# v2.net
KiCad netlist of a schematic drawn in EAGLE
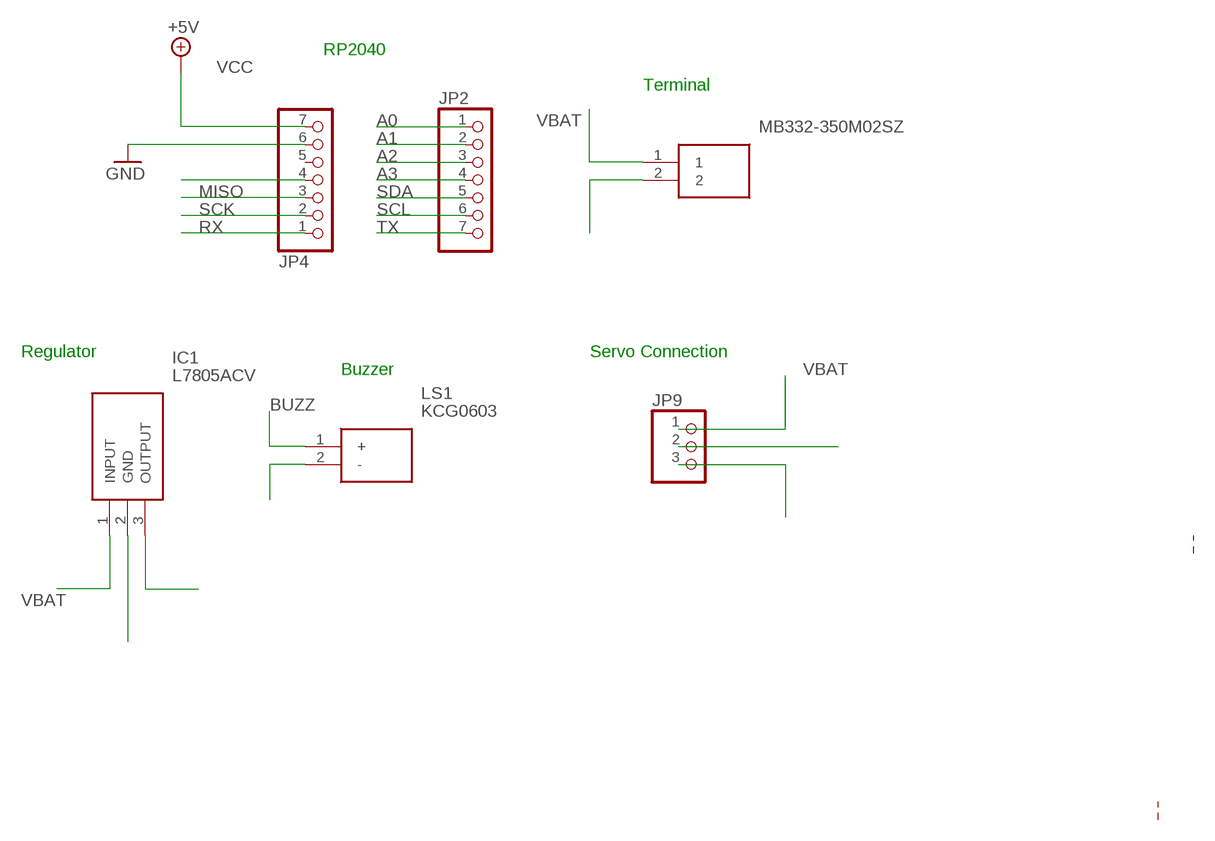
[diagram p0: schematic, sheet 1]

(export (version "E")
  (design (tool "Eeschema 10.0.6"))
  (components
    (comp (ref "IC1")
      (value "L7805ACV")
      (footprint "eagle-import:TO255P460X1020X2008-3P")
      (fields (field (name "RS_PART_NUMBER") "2988508P"))
      (libsource (lib "eagle-import") (part "L7805ACV"))
    )
    (comp (ref "JP2")
      (value "HEADER-1X7")
      (footprint "eagle-import:1X07_OVAL")
      (libsource (lib "eagle-import") (part "HEADER-1X7"))
    )
    (comp (ref "JP4")
      (value "HEADER-1X7")
      (footprint "eagle-import:1X07_OVAL")
      (libsource (lib "eagle-import") (part "HEADER-1X7"))
    )
    (comp (ref "JP9")
      (value "PINHD-1X3")
      (footprint "eagle-import:1X03")
      (libsource (lib "eagle-import") (part "PINHD-1X3"))
    )
    (comp (ref "LS1")
      (value "KCG0603")
      (footprint "eagle-import:CAPPRD320W70D660H400")
      (libsource (lib "eagle-import") (part "KCG0603"))
    )
    (comp (ref "VBAT")
      (value "MB332-350M02SZ")
      (footprint "eagle-import:MB332350M02SZ")
      (fields (field (name "RS_PART_NUMBER") "7901149"))
      (libsource (lib "eagle-import") (part "MB332-350M02SZ"))
    )
  )
  (nets
    (net (code "1") (name "+5V") (class "Default")
      (node (ref "JP4") (pin "7") (pinfunction "7_7") (pintype "passive"))
    )
    (net (code "2") (name "/A0") (class "Default")
      (node (ref "JP2") (pin "1") (pinfunction "1_1") (pintype "passive"))
    )
    (net (code "3") (name "/A1") (class "Default")
      (node (ref "JP2") (pin "2") (pinfunction "2_2") (pintype "passive"))
    )
    (net (code "4") (name "/A2") (class "Default")
      (node (ref "JP2") (pin "3") (pinfunction "3_3") (pintype "passive"))
    )
    (net (code "5") (name "/A3") (class "Default")
      (node (ref "JP2") (pin "4") (pinfunction "4_4") (pintype "passive"))
    )
    (net (code "6") (name "/BUZZ") (class "Default")
      (node (ref "LS1") (pin "1") (pinfunction "+_1") (pintype "bidirectional"))
    )
    (net (code "7") (name "/MISO") (class "Default")
      (node (ref "JP4") (pin "3") (pinfunction "3_3") (pintype "passive"))
    )
    (net (code "8") (name "/RX") (class "Default")
      (node (ref "JP4") (pin "1") (pinfunction "1_1") (pintype "passive"))
    )
    (net (code "9") (name "/SCK") (class "Default")
      (node (ref "JP4") (pin "2") (pinfunction "2_2") (pintype "passive"))
    )
    (net (code "10") (name "/SCL") (class "Default")
      (node (ref "JP2") (pin "6") (pinfunction "6_6") (pintype "passive"))
    )
    (net (code "11") (name "/SDA") (class "Default")
      (node (ref "JP2") (pin "5") (pinfunction "5_5") (pintype "passive"))
    )
    (net (code "12") (name "/TX") (class "Default")
      (node (ref "JP2") (pin "7") (pinfunction "7_7") (pintype "passive"))
    )
    (net (code "13") (name "/VBAT") (class "Default")
      (node (ref "IC1") (pin "1") (pinfunction "INPUT_1") (pintype "bidirectional"))
      (node (ref "JP9") (pin "1") (pinfunction "1_1") (pintype "passive"))
      (node (ref "VBAT") (pin "1") (pinfunction "1_1") (pintype "bidirectional"))
    )
    (net (code "14") (name "GND") (class "Default")
      (node (ref "JP4") (pin "6") (pinfunction "6_6") (pintype "passive"))
    )
    (net (code "15") (name "unconnected-(IC1-GND-Pad2)") (class "Default")
      (node (ref "IC1") (pin "2") (pinfunction "GND_2") (pintype "bidirectional"))
    )
    (net (code "16") (name "unconnected-(IC1-OUTPUT-Pad3)") (class "Default")
      (node (ref "IC1") (pin "3") (pinfunction "OUTPUT_3") (pintype "bidirectional"))
    )
    (net (code "17") (name "unconnected-(JP4-Pad4)") (class "Default")
      (node (ref "JP4") (pin "4") (pinfunction "4_4") (pintype "passive"))
    )
    (net (code "18") (name "unconnected-(JP4-Pad5)") (class "Default")
      (node (ref "JP4") (pin "5") (pinfunction "5_5") (pintype "passive"))
    )
    (net (code "19") (name "unconnected-(JP9-Pad2)") (class "Default")
      (node (ref "JP9") (pin "2") (pinfunction "2_2") (pintype "passive"))
    )
    (net (code "20") (name "unconnected-(JP9-Pad3)") (class "Default")
      (node (ref "JP9") (pin "3") (pinfunction "3_3") (pintype "passive"))
    )
    (net (code "21") (name "unconnected-(LS1---Pad2)") (class "Default")
      (node (ref "LS1") (pin "2") (pinfunction "-_2") (pintype "bidirectional"))
    )
    (net (code "22") (name "unconnected-(VBAT-Pad2)") (class "Default")
      (node (ref "VBAT") (pin "2") (pinfunction "2_2") (pintype "bidirectional"))
    )
  )
)
